# Lokalizator_GPS_GSM_Micha_Figo_uszka.net
KiCad netlist of a schematic drawn in EAGLE
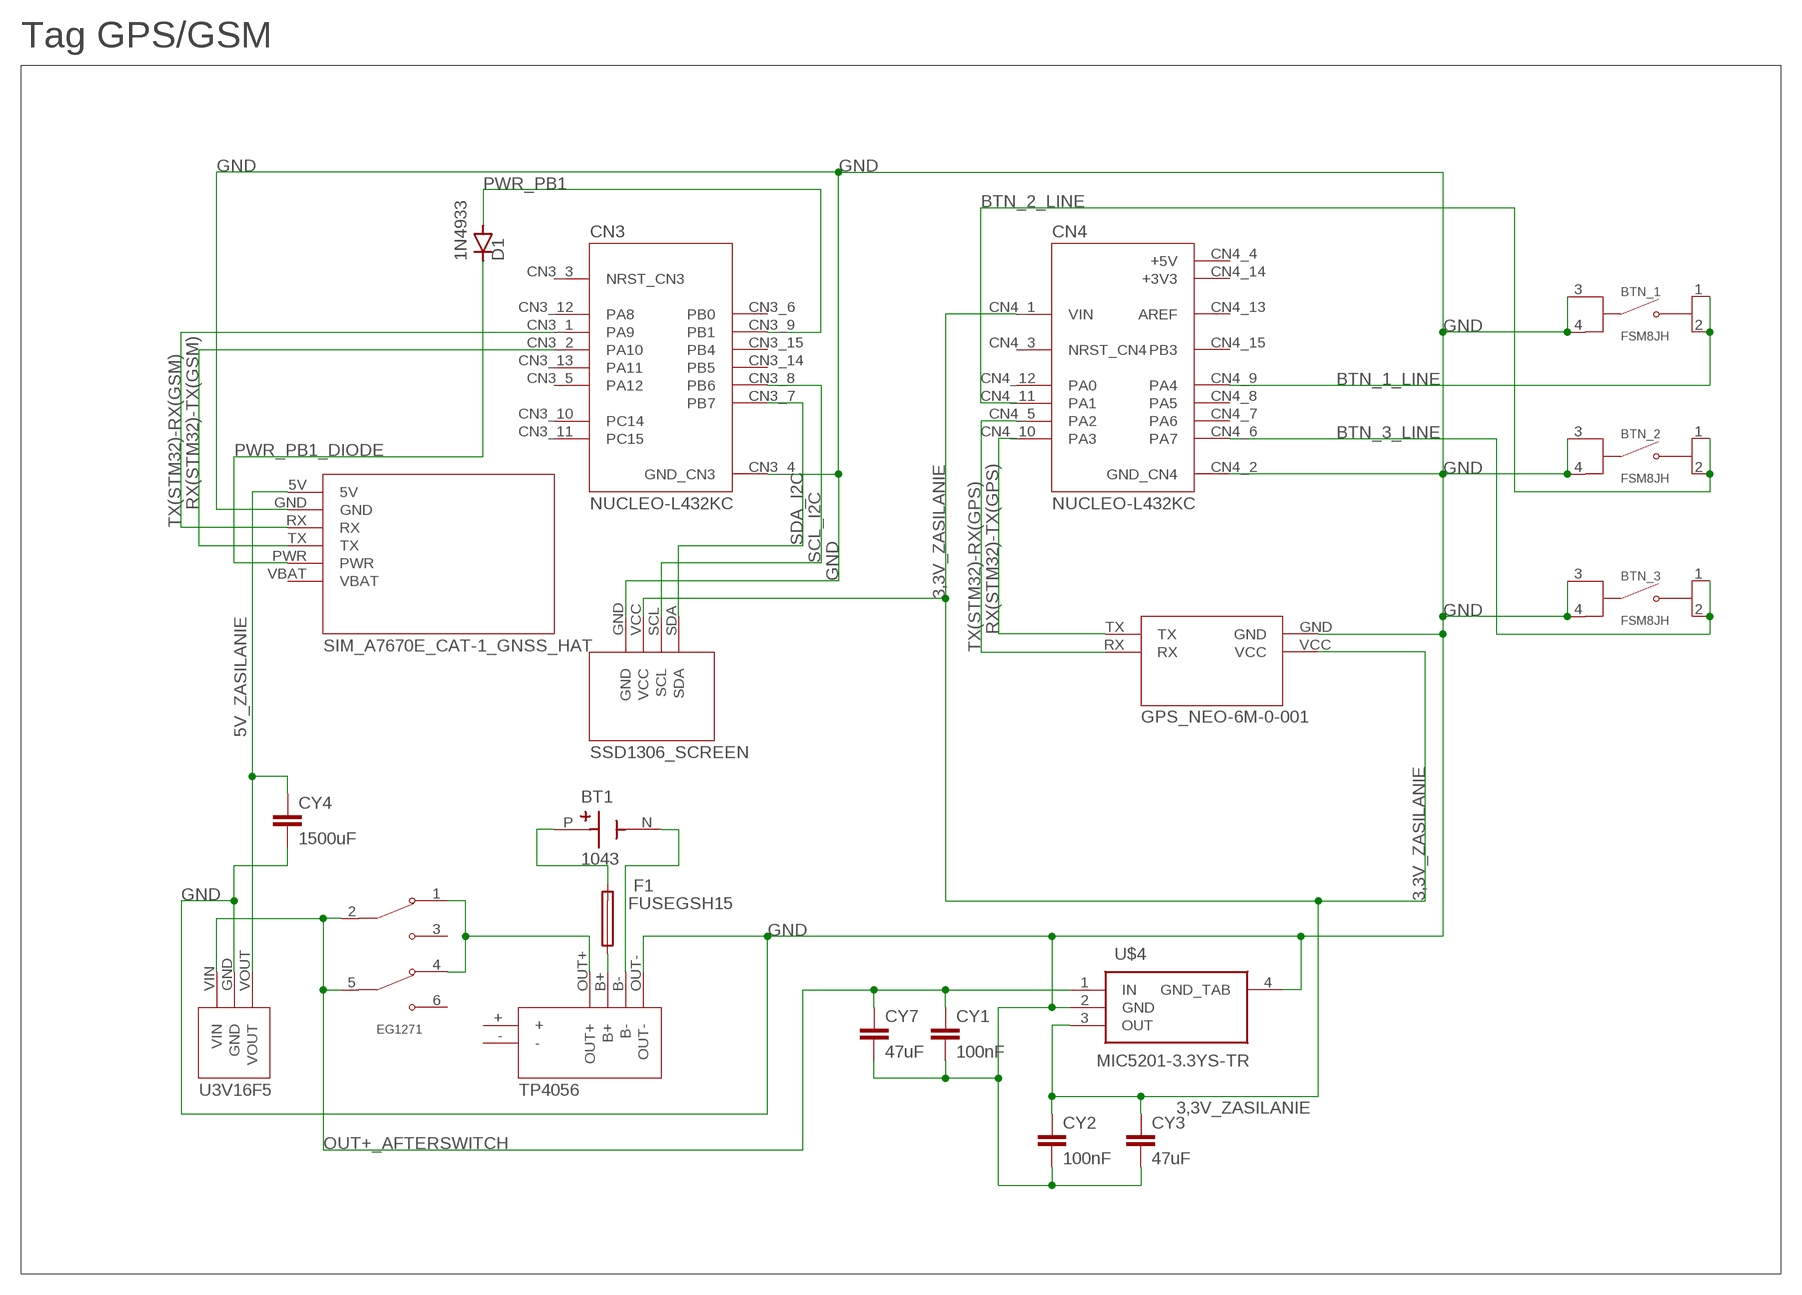
[diagram p0: schematic, sheet 1]

(export (version "E")
  (design (tool "Eeschema 10.0.6"))
  (components
    (comp (ref "BT1")
      (value "1043")
      (footprint "eagle-import:BAT_1043")
      (fields (field (name "MF") "Keystone Electronics"))
      (libsource (lib "eagle-import") (part "1043"))
    )
    (comp (ref "BTN_1")
      (value "FSM8JH")
      (footprint "eagle-import:SW_FSM8JH")
      (fields (field (name "MF") "TE Connectivity"))
      (libsource (lib "eagle-import") (part "FSM8JH"))
    )
    (comp (ref "BTN_2")
      (value "FSM8JH")
      (footprint "eagle-import:SW_FSM8JH")
      (fields (field (name "MF") "TE Connectivity"))
      (libsource (lib "eagle-import") (part "FSM8JH"))
    )
    (comp (ref "BTN_3")
      (value "FSM8JH")
      (footprint "eagle-import:SW_FSM8JH")
      (fields (field (name "MF") "TE Connectivity"))
      (libsource (lib "eagle-import") (part "FSM8JH"))
    )
    (comp (ref "CY1")
      (value "100nF")
      (footprint "eagle-import:YC7B5")
      (libsource (lib "eagle-import") (part "CYYC7B5"))
    )
    (comp (ref "CY2")
      (value "100nF")
      (footprint "eagle-import:YC7B5")
      (libsource (lib "eagle-import") (part "CYYC7B5"))
    )
    (comp (ref "CY3")
      (value "47uF")
      (footprint "eagle-import:YC7B5")
      (libsource (lib "eagle-import") (part "CYYC7B5"))
    )
    (comp (ref "CY4")
      (value "1500uF")
      (footprint "eagle-import:YC7B5")
      (libsource (lib "eagle-import") (part "CYYC7B5"))
    )
    (comp (ref "CY7")
      (value "47uF")
      (footprint "eagle-import:YC7B5")
      (libsource (lib "eagle-import") (part "CYYC7B5"))
    )
    (comp (ref "D1")
      (value "1N4933")
      (footprint "eagle-import:DO41-10")
      (libsource (lib "eagle-import") (part "1N4933"))
    )
    (comp (ref "F1")
      (value "FUSEGSH15")
      (footprint "eagle-import:GSH15")
      (libsource (lib "eagle-import") (part "FUSEGSH15"))
    )
    (comp (ref "S1")
      (value "EG1271")
      (footprint "eagle-import:SW_EG1271")
      (fields (field (name "MF") "E-Switch"))
      (libsource (lib "eagle-import") (part "EG1271"))
    )
    (comp (ref "U$1")
      (value "U3V16F5")
      (footprint "eagle-import:U3V16F5")
      (libsource (lib "eagle-import") (part "U3V16F5"))
    )
    (comp (ref "U$2")
      (value "TP4056")
      (footprint "eagle-import:TP4056")
      (libsource (lib "eagle-import") (part "TP4056"))
    )
    (comp (ref "U$3")
      (value "SSD1306_SCREEN")
      (footprint "eagle-import:SSD1306_SCREEN")
      (libsource (lib "eagle-import") (part "SSD1306_SCREEN"))
    )
    (comp (ref "U$4")
      (value "MIC5201-3.3YS-TR")
      (footprint "eagle-import:SOT230P700X180-4N")
      (libsource (lib "eagle-import") (part "MIC5201-3.3YS-TR"))
    )
    (comp (ref "U$6")
      (value "SIM7020E_NB-IOT_HAT")
      (footprint "eagle-import:SIM7020E_NB-IOT_HAT")
      (libsource (lib "eagle-import") (part "SIM7020E_NB-IOT_HAT"))
    )
    (comp (ref "U$7")
      (value "GPS_NEO-6M-0-001")
      (footprint "eagle-import:GPS_NEO-6M-0-001")
      (libsource (lib "eagle-import") (part "GPS_NEO-6M-0-001"))
    )
    (comp (ref "U1")
      (value "NUCLEO-L432KC")
      (footprint "eagle-import:MODULE_NUCLEO-L432KC")
      (fields (field (name "MF") "STMicroelectronics"))
      (libsource (lib "eagle-import") (part "NUCLEO-L432KC"))
    )
  )
  (nets
    (net (code "1") (name "/+3V3") (class "Default")
      (node (ref "U1") (pin "CN4_14") (pinfunction "+3V3_CN4_14") (pintype "power_in"))
    )
    (net (code "2") (name "/+5V") (class "Default")
      (node (ref "U1") (pin "CN4_4") (pinfunction "+5V_CN4_4") (pintype "power_in"))
    )
    (net (code "3") (name "/3,3V_ZASILANIE") (class "Default")
      (node (ref "CY2") (pin "1") (pinfunction "1_1") (pintype "passive"))
      (node (ref "CY3") (pin "1") (pinfunction "1_1") (pintype "passive"))
      (node (ref "U$3") (pin "VCC") (pinfunction "VCC_VCC") (pintype "bidirectional"))
      (node (ref "U$4") (pin "3") (pinfunction "OUT_3") (pintype "output"))
      (node (ref "U$7") (pin "VCC") (pinfunction "VCC_VCC") (pintype "bidirectional"))
      (node (ref "U1") (pin "CN4_1") (pinfunction "VIN_CN4_1") (pintype "input"))
    )
    (net (code "4") (name "/5V_ZASILANIE") (class "Default")
      (node (ref "CY4") (pin "1") (pinfunction "1_1") (pintype "passive"))
      (node (ref "U$1") (pin "VOUT") (pinfunction "VOUT_VOUT") (pintype "bidirectional"))
      (node (ref "U$6") (pin "5V") (pinfunction "5V_5V") (pintype "bidirectional"))
    )
    (net (code "5") (name "/BTN_1_LINE") (class "Default")
      (node (ref "BTN_1") (pin "1") (pinfunction "NO_1_1") (pintype "passive"))
      (node (ref "BTN_1") (pin "2") (pinfunction "NO_2_2") (pintype "passive"))
      (node (ref "U1") (pin "CN4_9") (pinfunction "PA4_CN4_9") (pintype "bidirectional"))
    )
    (net (code "6") (name "/BTN_2_LINE") (class "Default")
      (node (ref "BTN_2") (pin "1") (pinfunction "NO_1_1") (pintype "passive"))
      (node (ref "BTN_2") (pin "2") (pinfunction "NO_2_2") (pintype "passive"))
      (node (ref "U1") (pin "CN4_11") (pinfunction "PA1_CN4_11") (pintype "bidirectional"))
    )
    (net (code "7") (name "/BTN_3_LINE") (class "Default")
      (node (ref "BTN_3") (pin "1") (pinfunction "NO_1_1") (pintype "passive"))
      (node (ref "BTN_3") (pin "2") (pinfunction "NO_2_2") (pintype "passive"))
      (node (ref "U1") (pin "CN4_6") (pinfunction "PA7_CN4_6") (pintype "bidirectional"))
    )
    (net (code "8") (name "/GND") (class "Default")
      (node (ref "BTN_1") (pin "3") (pinfunction "COM_3_3") (pintype "passive"))
      (node (ref "BTN_1") (pin "4") (pinfunction "COM_4_4") (pintype "passive"))
      (node (ref "BTN_2") (pin "3") (pinfunction "COM_3_3") (pintype "passive"))
      (node (ref "BTN_2") (pin "4") (pinfunction "COM_4_4") (pintype "passive"))
      (node (ref "BTN_3") (pin "3") (pinfunction "COM_3_3") (pintype "passive"))
      (node (ref "BTN_3") (pin "4") (pinfunction "COM_4_4") (pintype "passive"))
      (node (ref "CY1") (pin "2") (pinfunction "2_2") (pintype "passive"))
      (node (ref "CY2") (pin "2") (pinfunction "2_2") (pintype "passive"))
      (node (ref "CY3") (pin "2") (pinfunction "2_2") (pintype "passive"))
      (node (ref "CY4") (pin "2") (pinfunction "2_2") (pintype "passive"))
      (node (ref "CY7") (pin "2") (pinfunction "2_2") (pintype "passive"))
      (node (ref "U$1") (pin "GND") (pinfunction "GND_GND") (pintype "bidirectional"))
      (node (ref "U$2") (pin "OUT-") (pinfunction "OUT-_OUT-") (pintype "bidirectional"))
      (node (ref "U$3") (pin "GND") (pinfunction "GND_GND") (pintype "bidirectional"))
      (node (ref "U$4") (pin "2") (pinfunction "GND_2") (pintype "power_in"))
      (node (ref "U$4") (pin "4") (pinfunction "GND_TAB_4") (pintype "power_in"))
      (node (ref "U$6") (pin "GND") (pinfunction "GND_GND") (pintype "bidirectional"))
      (node (ref "U$7") (pin "GND") (pinfunction "GND_GND") (pintype "bidirectional"))
      (node (ref "U1") (pin "CN3_4") (pinfunction "GND_CN3_CN3_4") (pintype "power_in"))
      (node (ref "U1") (pin "CN4_2") (pinfunction "GND_CN4_CN4_2") (pintype "power_in"))
    )
    (net (code "9") (name "/OUT+_AFTERSWITCH") (class "Default")
      (node (ref "CY1") (pin "1") (pinfunction "1_1") (pintype "passive"))
      (node (ref "CY7") (pin "1") (pinfunction "1_1") (pintype "passive"))
      (node (ref "S1") (pin "2") (pinfunction "COM1_2") (pintype "passive"))
      (node (ref "S1") (pin "5") (pinfunction "COM2_5") (pintype "passive"))
      (node (ref "U$1") (pin "VIN") (pinfunction "VIN_VIN") (pintype "bidirectional"))
      (node (ref "U$4") (pin "1") (pinfunction "IN_1") (pintype "input"))
    )
    (net (code "10") (name "/PWR_PB1") (class "Default")
      (node (ref "D1") (pin "A") (pinfunction "A_A") (pintype "passive"))
      (node (ref "U1") (pin "CN3_9") (pinfunction "PB1_CN3_9") (pintype "bidirectional"))
    )
    (net (code "11") (name "/PWR_PB1_DIODE") (class "Default")
      (node (ref "D1") (pin "C") (pinfunction "C_C") (pintype "passive"))
      (node (ref "U$6") (pin "PWR") (pinfunction "PWR_PWR") (pintype "bidirectional"))
    )
    (net (code "12") (name "/RX(STM32)-TX(GPS)") (class "Default")
      (node (ref "U$7") (pin "TX") (pinfunction "TX_TX") (pintype "bidirectional"))
      (node (ref "U1") (pin "CN4_10") (pinfunction "PA3_CN4_10") (pintype "bidirectional"))
    )
    (net (code "13") (name "/RX(STM32)-TX(GSM)") (class "Default")
      (node (ref "U$6") (pin "TX") (pinfunction "TX_TX") (pintype "bidirectional"))
      (node (ref "U1") (pin "CN3_2") (pinfunction "PA10_CN3_2") (pintype "bidirectional"))
    )
    (net (code "14") (name "/SCL_I2C") (class "Default")
      (node (ref "U$3") (pin "SCL") (pinfunction "SCL_SCL") (pintype "bidirectional"))
      (node (ref "U1") (pin "CN3_8") (pinfunction "PB6_CN3_8") (pintype "bidirectional"))
    )
    (net (code "15") (name "/SDA_I2C") (class "Default")
      (node (ref "U$3") (pin "SDA") (pinfunction "SDA_SDA") (pintype "bidirectional"))
      (node (ref "U1") (pin "CN3_7") (pinfunction "PB7_CN3_7") (pintype "bidirectional"))
    )
    (net (code "16") (name "/TX(STM32)-RX(GPS)") (class "Default")
      (node (ref "U$7") (pin "RX") (pinfunction "RX_RX") (pintype "bidirectional"))
      (node (ref "U1") (pin "CN4_5") (pinfunction "PA2_CN4_5") (pintype "bidirectional"))
    )
    (net (code "17") (name "/TX(STM32)-RX(GSM)") (class "Default")
      (node (ref "U$6") (pin "RX") (pinfunction "RX_RX") (pintype "bidirectional"))
      (node (ref "U1") (pin "CN3_1") (pinfunction "PA9_CN3_1") (pintype "bidirectional"))
    )
    (net (code "18") (name "Net-(BT1-NEG)") (class "Default")
      (node (ref "BT1") (pin "N") (pinfunction "NEG_N") (pintype "passive"))
      (node (ref "U$2") (pin "B-") (pinfunction "B-_B-") (pintype "bidirectional"))
    )
    (net (code "19") (name "Net-(BT1-POS)") (class "Default")
      (node (ref "BT1") (pin "P") (pinfunction "POS_P") (pintype "passive"))
      (node (ref "F1") (pin "2") (pinfunction "2_2") (pintype "passive"))
    )
    (net (code "20") (name "Net-(F1-Pad1)") (class "Default")
      (node (ref "F1") (pin "1") (pinfunction "1_1") (pintype "passive"))
      (node (ref "U$2") (pin "B+") (pinfunction "B+_B+") (pintype "bidirectional"))
    )
    (net (code "21") (name "Net-(S1-NC1)") (class "Default")
      (node (ref "S1") (pin "1") (pinfunction "NC1_1") (pintype "passive"))
      (node (ref "S1") (pin "4") (pinfunction "NC2_4") (pintype "passive"))
      (node (ref "U$2") (pin "OUT+") (pinfunction "OUT+_OUT+") (pintype "bidirectional"))
    )
    (net (code "22") (name "unconnected-(S1-NO1-Pad3)") (class "Default")
      (node (ref "S1") (pin "3") (pinfunction "NO1_3") (pintype "passive"))
    )
    (net (code "23") (name "unconnected-(S1-NO2-Pad6)") (class "Default")
      (node (ref "S1") (pin "6") (pinfunction "NO2_6") (pintype "passive"))
    )
    (net (code "24") (name "unconnected-(U$2-Pad+)") (class "Default")
      (node (ref "U$2") (pin "+") (pinfunction "+_+") (pintype "bidirectional"))
    )
    (net (code "25") (name "unconnected-(U$2-Pad-)") (class "Default")
      (node (ref "U$2") (pin "-") (pinfunction "-_-") (pintype "bidirectional"))
    )
    (net (code "26") (name "unconnected-(U$6-PadVBAT)") (class "Default")
      (node (ref "U$6") (pin "VBAT") (pinfunction "VBAT_VBAT") (pintype "bidirectional"))
    )
    (net (code "27") (name "unconnected-(U1A-NRST_CN3-PadCN3_3)") (class "Default")
      (node (ref "U1") (pin "CN3_3") (pinfunction "NRST_CN3_CN3_3") (pintype "bidirectional"))
    )
    (net (code "28") (name "unconnected-(U1A-PA8-PadCN3_12)") (class "Default")
      (node (ref "U1") (pin "CN3_12") (pinfunction "PA8_CN3_12") (pintype "bidirectional"))
    )
    (net (code "29") (name "unconnected-(U1A-PA11-PadCN3_13)") (class "Default")
      (node (ref "U1") (pin "CN3_13") (pinfunction "PA11_CN3_13") (pintype "bidirectional"))
    )
    (net (code "30") (name "unconnected-(U1A-PA12-PadCN3_5)") (class "Default")
      (node (ref "U1") (pin "CN3_5") (pinfunction "PA12_CN3_5") (pintype "bidirectional"))
    )
    (net (code "31") (name "unconnected-(U1A-PB0-PadCN3_6)") (class "Default")
      (node (ref "U1") (pin "CN3_6") (pinfunction "PB0_CN3_6") (pintype "bidirectional"))
    )
    (net (code "32") (name "unconnected-(U1A-PB4-PadCN3_15)") (class "Default")
      (node (ref "U1") (pin "CN3_15") (pinfunction "PB4_CN3_15") (pintype "bidirectional"))
    )
    (net (code "33") (name "unconnected-(U1A-PB5-PadCN3_14)") (class "Default")
      (node (ref "U1") (pin "CN3_14") (pinfunction "PB5_CN3_14") (pintype "bidirectional"))
    )
    (net (code "34") (name "unconnected-(U1A-PC14-PadCN3_10)") (class "Default")
      (node (ref "U1") (pin "CN3_10") (pinfunction "PC14_CN3_10") (pintype "bidirectional"))
    )
    (net (code "35") (name "unconnected-(U1A-PC15-PadCN3_11)") (class "Default")
      (node (ref "U1") (pin "CN3_11") (pinfunction "PC15_CN3_11") (pintype "bidirectional"))
    )
    (net (code "36") (name "unconnected-(U1B-AREF-PadCN4_13)") (class "Default")
      (node (ref "U1") (pin "CN4_13") (pinfunction "AREF_CN4_13") (pintype "bidirectional"))
    )
    (net (code "37") (name "unconnected-(U1B-NRST_CN4-PadCN4_3)") (class "Default")
      (node (ref "U1") (pin "CN4_3") (pinfunction "NRST_CN4_CN4_3") (pintype "bidirectional"))
    )
    (net (code "38") (name "unconnected-(U1B-PA0-PadCN4_12)") (class "Default")
      (node (ref "U1") (pin "CN4_12") (pinfunction "PA0_CN4_12") (pintype "bidirectional"))
    )
    (net (code "39") (name "unconnected-(U1B-PA5-PadCN4_8)") (class "Default")
      (node (ref "U1") (pin "CN4_8") (pinfunction "PA5_CN4_8") (pintype "bidirectional"))
    )
    (net (code "40") (name "unconnected-(U1B-PA6-PadCN4_7)") (class "Default")
      (node (ref "U1") (pin "CN4_7") (pinfunction "PA6_CN4_7") (pintype "bidirectional"))
    )
    (net (code "41") (name "unconnected-(U1B-PB3-PadCN4_15)") (class "Default")
      (node (ref "U1") (pin "CN4_15") (pinfunction "PB3_CN4_15") (pintype "bidirectional"))
    )
  )
)
